# max7219_breakout.net
KiCad netlist of a schematic drawn in EAGLE
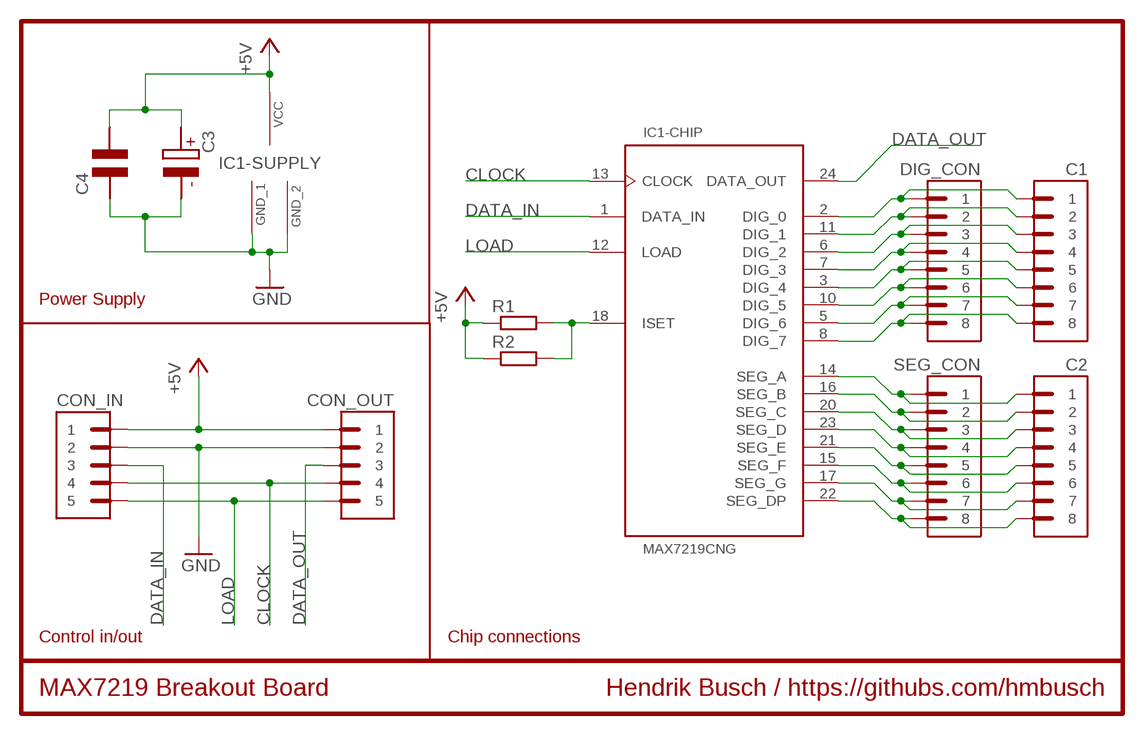
[diagram p0: schematic, sheet 1]

(export (version "E")
  (design (tool "Eeschema 10.0.6"))
  (components
    (comp (ref "C1")
      (value "PIN_HEADER_8-SCREW-TERMINAL")
      (footprint "eagle-import:TERMINAL_BLOCK_8")
      (libsource (lib "eagle-import") (part "PIN_HEADER_8-SCREW-TERMINAL"))
    )
    (comp (ref "C2")
      (value "PIN_HEADER_8-SCREW-TERMINAL")
      (footprint "eagle-import:TERMINAL_BLOCK_8")
      (libsource (lib "eagle-import") (part "PIN_HEADER_8-SCREW-TERMINAL"))
    )
    (comp (ref "C3")
      (value "CAPACITOR_POLARIZED-5X5-2.0")
      (footprint "eagle-import:CAP_POL_5X5_2")
      (libsource (lib "eagle-import") (part "CAPACITOR_POLARIZED-5X5-2.0"))
    )
    (comp (ref "C4")
      (value "CAPACITOR-CERAMIC-5MM")
      (footprint "eagle-import:CERAMIC_CAP_5MM")
      (libsource (lib "eagle-import") (part "CAPACITOR-CERAMIC-5MM"))
    )
    (comp (ref "CON_IN")
      (value "PIN_HEADER_5-WIDE")
      (footprint "eagle-import:BREAKAWAY_STRAIGHT_5_WIDE")
      (libsource (lib "eagle-import") (part "PIN_HEADER_5-WIDE"))
    )
    (comp (ref "CON_OUT")
      (value "PIN_HEADER_5-WIDE")
      (footprint "eagle-import:BREAKAWAY_STRAIGHT_5_WIDE")
      (libsource (lib "eagle-import") (part "PIN_HEADER_5-WIDE"))
    )
    (comp (ref "DIG_CON")
      (value "PIN_HEADER_8-WIDE")
      (footprint "eagle-import:BREAKAWAY_STRAIGHT_8_WIDE")
      (libsource (lib "eagle-import") (part "PIN_HEADER_8-WIDE"))
    )
    (comp (ref "IC1")
      (value "MAX7219CNG")
      (footprint "eagle-import:DIP-24")
      (libsource (lib "eagle-import") (part "MAX7219CNG"))
    )
    (comp (ref "R1")
      (value "RESISTOR-1/4W-12.7-AXIAL")
      (footprint "eagle-import:RESISTOR-1_4W-AXIAL")
      (libsource (lib "eagle-import") (part "RESISTOR-1/4W-12.7-AXIAL"))
    )
    (comp (ref "R2")
      (value "RESISTOR-1/4W-12.7-AXIAL")
      (footprint "eagle-import:RESISTOR-1_4W-AXIAL")
      (libsource (lib "eagle-import") (part "RESISTOR-1/4W-12.7-AXIAL"))
    )
    (comp (ref "SEG_CON")
      (value "PIN_HEADER_8-WIDE")
      (footprint "eagle-import:BREAKAWAY_STRAIGHT_8_WIDE")
      (libsource (lib "eagle-import") (part "PIN_HEADER_8-WIDE"))
    )
  )
  (nets
    (net (code "1") (name "+5V") (class "Default")
      (node (ref "C3") (pin "A") (pinfunction "A_A") (pintype "passive"))
      (node (ref "C4") (pin "P$2") (pinfunction "P$2_P$2") (pintype "passive"))
      (node (ref "CON_IN") (pin "1") (pinfunction "1_1") (pintype "passive"))
      (node (ref "CON_OUT") (pin "1") (pinfunction "1_1") (pintype "passive"))
      (node (ref "IC1") (pin "19") (pinfunction "VCC_19") (pintype "power_in"))
      (node (ref "R1") (pin "P$1") (pinfunction "1_P$1") (pintype "passive"))
      (node (ref "R2") (pin "P$1") (pinfunction "1_P$1") (pintype "passive"))
    )
    (net (code "2") (name "/CLOCK") (class "Default")
      (node (ref "CON_IN") (pin "4") (pinfunction "4_4") (pintype "passive"))
      (node (ref "CON_OUT") (pin "4") (pinfunction "4_4") (pintype "passive"))
      (node (ref "IC1") (pin "13") (pinfunction "CLOCK_13") (pintype "input"))
    )
    (net (code "3") (name "/DATA_IN") (class "Default")
      (node (ref "CON_IN") (pin "3") (pinfunction "3_3") (pintype "passive"))
      (node (ref "IC1") (pin "1") (pinfunction "DATA_IN_1") (pintype "input"))
    )
    (net (code "4") (name "/DATA_OUT") (class "Default")
      (node (ref "CON_OUT") (pin "3") (pinfunction "3_3") (pintype "passive"))
      (node (ref "IC1") (pin "24") (pinfunction "DATA_OUT_24") (pintype "output"))
    )
    (net (code "5") (name "/LOAD") (class "Default")
      (node (ref "CON_IN") (pin "5") (pinfunction "5_5") (pintype "passive"))
      (node (ref "CON_OUT") (pin "5") (pinfunction "5_5") (pintype "passive"))
      (node (ref "IC1") (pin "12") (pinfunction "LOAD_12") (pintype "input"))
    )
    (net (code "6") (name "GND") (class "Default")
      (node (ref "C3") (pin "C") (pinfunction "C_C") (pintype "passive"))
      (node (ref "C4") (pin "P$1") (pinfunction "P$1_P$1") (pintype "passive"))
      (node (ref "CON_IN") (pin "2") (pinfunction "2_2") (pintype "passive"))
      (node (ref "CON_OUT") (pin "2") (pinfunction "2_2") (pintype "passive"))
      (node (ref "IC1") (pin "4") (pinfunction "GND_1_4") (pintype "power_in"))
      (node (ref "IC1") (pin "9") (pinfunction "GND_2_9") (pintype "power_in"))
    )
    (net (code "7") (name "Net-(C1-1)") (class "Default")
      (node (ref "C1") (pin "P$1") (pinfunction "1_P$1") (pintype "bidirectional"))
      (node (ref "DIG_CON") (pin "1") (pinfunction "1_1") (pintype "bidirectional"))
      (node (ref "IC1") (pin "2") (pinfunction "DIG_0_2") (pintype "input"))
    )
    (net (code "8") (name "Net-(C1-2)") (class "Default")
      (node (ref "C1") (pin "P$2") (pinfunction "2_P$2") (pintype "bidirectional"))
      (node (ref "DIG_CON") (pin "2") (pinfunction "2_2") (pintype "bidirectional"))
      (node (ref "IC1") (pin "11") (pinfunction "DIG_1_11") (pintype "input"))
    )
    (net (code "9") (name "Net-(C1-3)") (class "Default")
      (node (ref "C1") (pin "P$3") (pinfunction "3_P$3") (pintype "bidirectional"))
      (node (ref "DIG_CON") (pin "3") (pinfunction "3_3") (pintype "bidirectional"))
      (node (ref "IC1") (pin "6") (pinfunction "DIG_2_6") (pintype "input"))
    )
    (net (code "10") (name "Net-(C1-4)") (class "Default")
      (node (ref "C1") (pin "P$4") (pinfunction "4_P$4") (pintype "bidirectional"))
      (node (ref "DIG_CON") (pin "4") (pinfunction "4_4") (pintype "bidirectional"))
      (node (ref "IC1") (pin "7") (pinfunction "DIG_3_7") (pintype "input"))
    )
    (net (code "11") (name "Net-(C1-5)") (class "Default")
      (node (ref "C1") (pin "P$5") (pinfunction "5_P$5") (pintype "bidirectional"))
      (node (ref "DIG_CON") (pin "5") (pinfunction "5_5") (pintype "bidirectional"))
      (node (ref "IC1") (pin "3") (pinfunction "DIG_4_3") (pintype "input"))
    )
    (net (code "12") (name "Net-(C1-6)") (class "Default")
      (node (ref "C1") (pin "P$6") (pinfunction "6_P$6") (pintype "bidirectional"))
      (node (ref "DIG_CON") (pin "6") (pinfunction "6_6") (pintype "bidirectional"))
      (node (ref "IC1") (pin "10") (pinfunction "DIG_5_10") (pintype "input"))
    )
    (net (code "13") (name "Net-(C1-7)") (class "Default")
      (node (ref "C1") (pin "P$7") (pinfunction "7_P$7") (pintype "bidirectional"))
      (node (ref "DIG_CON") (pin "7") (pinfunction "7_7") (pintype "bidirectional"))
      (node (ref "IC1") (pin "5") (pinfunction "DIG_6_5") (pintype "input"))
    )
    (net (code "14") (name "Net-(C1-8)") (class "Default")
      (node (ref "C1") (pin "P$8") (pinfunction "8_P$8") (pintype "bidirectional"))
      (node (ref "DIG_CON") (pin "8") (pinfunction "8_8") (pintype "bidirectional"))
      (node (ref "IC1") (pin "8") (pinfunction "DIG_7_8") (pintype "input"))
    )
    (net (code "15") (name "Net-(C2-1)") (class "Default")
      (node (ref "C2") (pin "P$1") (pinfunction "1_P$1") (pintype "bidirectional"))
      (node (ref "IC1") (pin "14") (pinfunction "SEG_A_14") (pintype "output"))
      (node (ref "SEG_CON") (pin "1") (pinfunction "1_1") (pintype "bidirectional"))
    )
    (net (code "16") (name "Net-(C2-2)") (class "Default")
      (node (ref "C2") (pin "P$2") (pinfunction "2_P$2") (pintype "bidirectional"))
      (node (ref "IC1") (pin "16") (pinfunction "SEG_B_16") (pintype "output"))
      (node (ref "SEG_CON") (pin "2") (pinfunction "2_2") (pintype "bidirectional"))
    )
    (net (code "17") (name "Net-(C2-3)") (class "Default")
      (node (ref "C2") (pin "P$3") (pinfunction "3_P$3") (pintype "bidirectional"))
      (node (ref "IC1") (pin "20") (pinfunction "SEG_C_20") (pintype "output"))
      (node (ref "SEG_CON") (pin "3") (pinfunction "3_3") (pintype "bidirectional"))
    )
    (net (code "18") (name "Net-(C2-4)") (class "Default")
      (node (ref "C2") (pin "P$4") (pinfunction "4_P$4") (pintype "bidirectional"))
      (node (ref "IC1") (pin "23") (pinfunction "SEG_D_23") (pintype "output"))
      (node (ref "SEG_CON") (pin "4") (pinfunction "4_4") (pintype "bidirectional"))
    )
    (net (code "19") (name "Net-(C2-5)") (class "Default")
      (node (ref "C2") (pin "P$5") (pinfunction "5_P$5") (pintype "bidirectional"))
      (node (ref "IC1") (pin "21") (pinfunction "SEG_E_21") (pintype "output"))
      (node (ref "SEG_CON") (pin "5") (pinfunction "5_5") (pintype "bidirectional"))
    )
    (net (code "20") (name "Net-(C2-6)") (class "Default")
      (node (ref "C2") (pin "P$6") (pinfunction "6_P$6") (pintype "bidirectional"))
      (node (ref "IC1") (pin "15") (pinfunction "SEG_F_15") (pintype "output"))
      (node (ref "SEG_CON") (pin "6") (pinfunction "6_6") (pintype "bidirectional"))
    )
    (net (code "21") (name "Net-(C2-7)") (class "Default")
      (node (ref "C2") (pin "P$7") (pinfunction "7_P$7") (pintype "bidirectional"))
      (node (ref "IC1") (pin "17") (pinfunction "SEG_G_17") (pintype "bidirectional"))
      (node (ref "SEG_CON") (pin "7") (pinfunction "7_7") (pintype "bidirectional"))
    )
    (net (code "22") (name "Net-(C2-8)") (class "Default")
      (node (ref "C2") (pin "P$8") (pinfunction "8_P$8") (pintype "bidirectional"))
      (node (ref "IC1") (pin "22") (pinfunction "SEG_DP_22") (pintype "output"))
      (node (ref "SEG_CON") (pin "8") (pinfunction "8_8") (pintype "bidirectional"))
    )
    (net (code "23") (name "Net-(IC1A-ISET)") (class "Default")
      (node (ref "IC1") (pin "18") (pinfunction "ISET_18") (pintype "input"))
      (node (ref "R1") (pin "P$2") (pinfunction "2_P$2") (pintype "passive"))
      (node (ref "R2") (pin "P$2") (pinfunction "2_P$2") (pintype "passive"))
    )
  )
)
